# 02cpu_power.net
KiCad netlist of a schematic drawn in Altium Designer
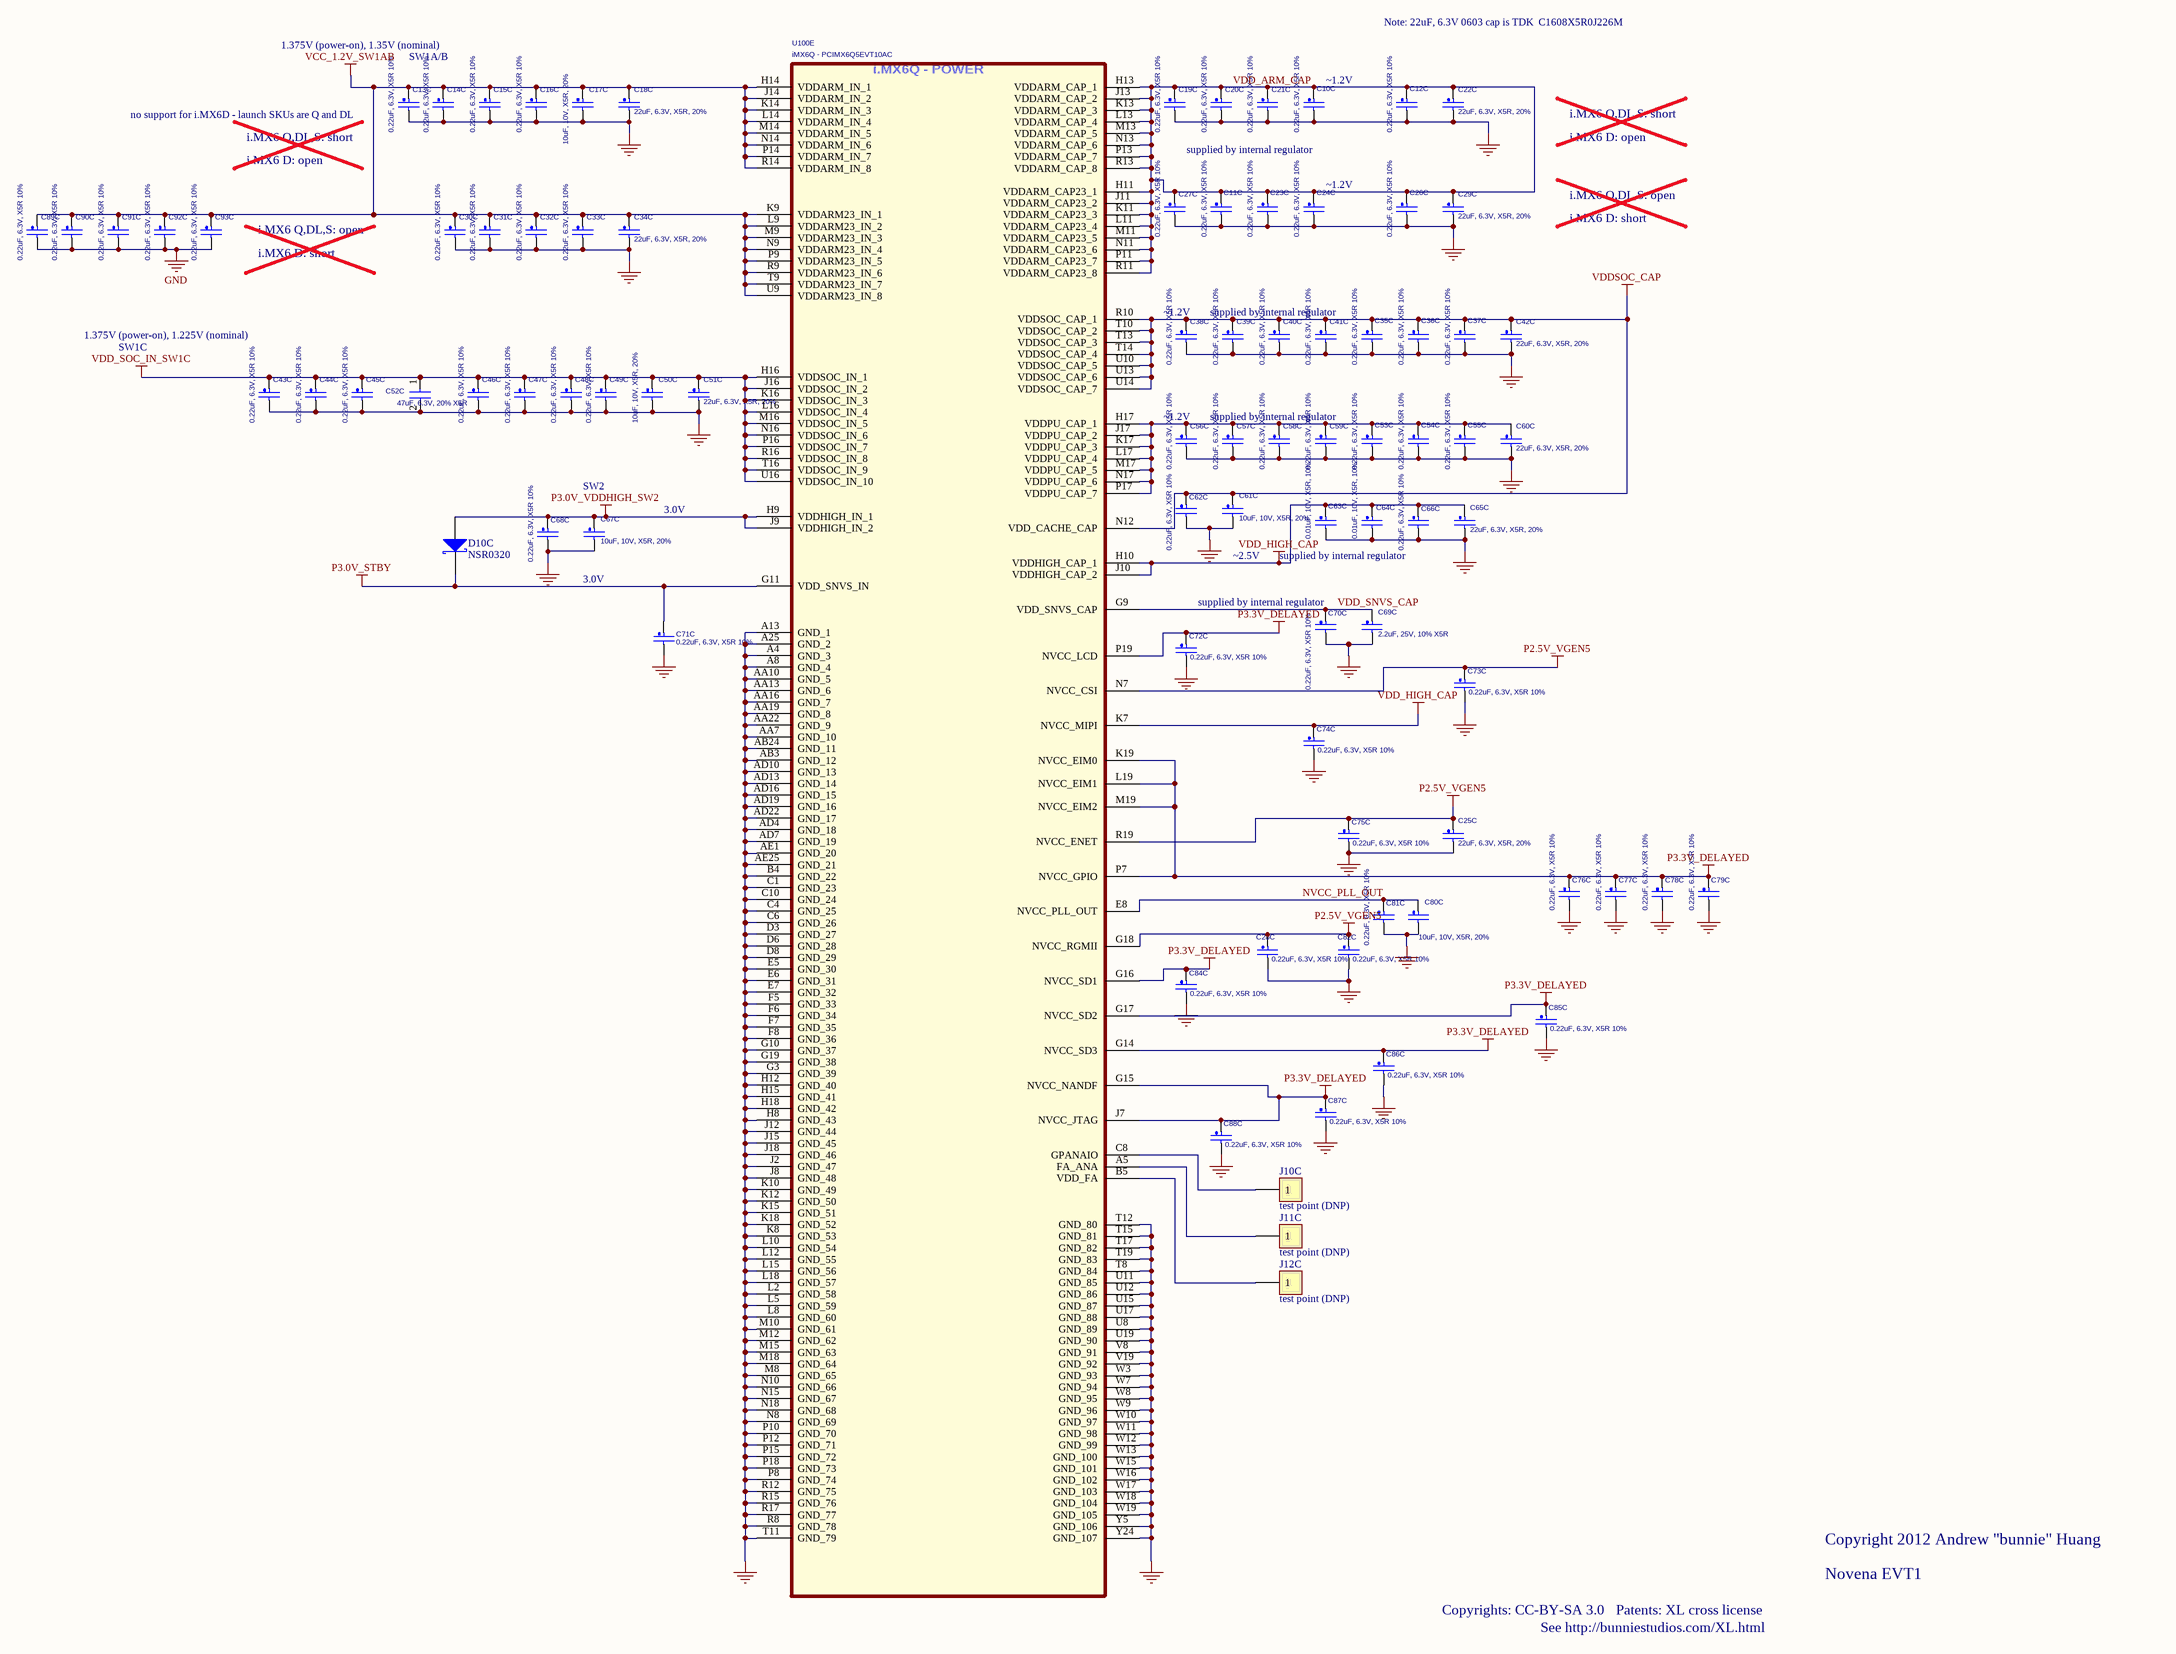
[diagram p0: 02cpu_power.SchDoc]

(export (version "E")
  (design (tool "Eeschema 10.0.6"))
  (components
    (comp (ref "C10C")
      (value "0.22uF, 6.3V, X5R 10%")
      (footprint "CAPC0603N_B")
      (description "CAP CER 0.01UF 6.3V 10% X7R 0201")
      (fields (field (name "TOLERANCE") "10%"))
      (libsource (lib "*") (part "CAP_NP_Dup1"))
    )
    (comp (ref "C11C")
      (value "0.22uF, 6.3V, X5R 10%")
      (footprint "CAPC0603N_B")
      (description "CAP CER 0.01UF 6.3V 10% X7R 0201")
      (fields (field (name "TOLERANCE") "10%"))
      (libsource (lib "*") (part "CAP_NP_Dup1"))
    )
    (comp (ref "C12C")
      (value "0.22uF, 6.3V, X5R 10%")
      (footprint "CAPC0603N_B")
      (description "CAP CER 0.01UF 6.3V 10% X7R 0201")
      (fields (field (name "TOLERANCE") "10%"))
      (libsource (lib "*") (part "CAP_NP_Dup1"))
    )
    (comp (ref "C13C")
      (value "0.22uF, 6.3V, X5R 10%")
      (footprint "CAPC0603N_B")
      (description "CAP CER 0.22UF 6.3V 20% X5R 0201")
      (fields (field (name "TOLERANCE") "20%"))
      (libsource (lib "*") (part "CAP_NP_Dup1"))
    )
    (comp (ref "C14C")
      (value "0.22uF, 6.3V, X5R 10%")
      (footprint "CAPC0603N_B")
      (description "CAP CER 0.22UF 6.3V 20% X5R 0201")
      (fields (field (name "TOLERANCE") "20%"))
      (libsource (lib "*") (part "CAP_NP_Dup1"))
    )
    (comp (ref "C15C")
      (value "0.22uF, 6.3V, X5R 10%")
      (footprint "CAPC0603N_B")
      (description "CAP CER 0.22UF 6.3V 20% X5R 0201")
      (fields (field (name "TOLERANCE") "20%"))
      (libsource (lib "*") (part "CAP_NP_Dup1"))
    )
    (comp (ref "C16C")
      (value "0.22uF, 6.3V, X5R 10%")
      (footprint "CAPC0603N_B")
      (description "CAP CER 0.22UF 6.3V 20% X5R 0201")
      (fields (field (name "TOLERANCE") "20%"))
      (libsource (lib "*") (part "CAP_NP_Dup1"))
    )
    (comp (ref "C17C")
      (value "10uF, 10V, X5R, 20%")
      (footprint "CAPC1608N_HD")
      (description "CAP CER 10UF 6.3V 10% X5R 0603")
      (fields (field (name "TOLERANCE") "10%"))
      (libsource (lib "*") (part "CAP_NP_Dup1"))
    )
    (comp (ref "C18C")
      (value "22uF, 6.3V, X5R, 20%")
      (footprint "CAPC1608N_HD")
      (description "CAP CER 22UF 6.3V 20% X5R 0805")
      (fields (field (name "TOLERANCE") "20%"))
      (libsource (lib "*") (part "CAP_NP_Dup1"))
    )
    (comp (ref "C19C")
      (value "0.22uF, 6.3V, X5R 10%")
      (footprint "CAPC0603N_B")
      (description "CAP CER 0.22UF 6.3V 20% X5R 0201")
      (fields (field (name "TOLERANCE") "20%"))
      (libsource (lib "*") (part "CAP_NP_Dup1"))
    )
    (comp (ref "C20C")
      (value "0.22uF, 6.3V, X5R 10%")
      (footprint "CAPC0603N_B")
      (description "CAP CER 0.22UF 6.3V 20% X5R 0201")
      (fields (field (name "TOLERANCE") "20%"))
      (libsource (lib "*") (part "CAP_NP_Dup1"))
    )
    (comp (ref "C21C")
      (value "0.22uF, 6.3V, X5R 10%")
      (footprint "CAPC0603N_B")
      (description "CAP CER 0.22UF 6.3V 20% X5R 0201")
      (fields (field (name "TOLERANCE") "20%"))
      (libsource (lib "*") (part "CAP_NP_Dup1"))
    )
    (comp (ref "C22C")
      (value "22uF, 6.3V, X5R, 20%")
      (footprint "CAPC1608N_HD")
      (description "CAP CER 22UF 6.3V 20% X5R 0805")
      (fields (field (name "TOLERANCE") "20%"))
      (libsource (lib "*") (part "CAP_NP_Dup1"))
    )
    (comp (ref "C23C")
      (value "0.22uF, 6.3V, X5R 10%")
      (footprint "CAPC0603N_B")
      (description "CAP CER 0.22UF 6.3V 20% X5R 0201")
      (fields (field (name "TOLERANCE") "20%"))
      (libsource (lib "*") (part "CAP_NP_Dup1"))
    )
    (comp (ref "C24C")
      (value "0.22uF, 6.3V, X5R 10%")
      (footprint "CAPC0603N_B")
      (description "CAP CER 0.01UF 6.3V 10% X7R 0201")
      (fields (field (name "TOLERANCE") "10%"))
      (libsource (lib "*") (part "CAP_NP_Dup1"))
    )
    (comp (ref "C25C")
      (value "22uF, 6.3V, X5R, 20%")
      (footprint "CAPC1608N_HD")
      (description "CAP CER 22UF 6.3V 20% X5R 0805")
      (fields (field (name "TOLERANCE") "20%"))
      (libsource (lib "*") (part "CAP_NP_Dup1"))
    )
    (comp (ref "C26C")
      (value "0.22uF, 6.3V, X5R 10%")
      (footprint "CAPC0603N_B")
      (description "CAP CER 0.01UF 6.3V 10% X7R 0201")
      (fields (field (name "TOLERANCE") "10%"))
      (libsource (lib "*") (part "CAP_NP_Dup1"))
    )
    (comp (ref "C27C")
      (value "0.22uF, 6.3V, X5R 10%")
      (footprint "CAPC0603N_B")
      (description "CAP CER 0.22UF 6.3V 20% X5R 0201")
      (fields (field (name "TOLERANCE") "20%"))
      (libsource (lib "*") (part "CAP_NP_Dup1"))
    )
    (comp (ref "C28C")
      (value "0.22uF, 6.3V, X5R 10%")
      (footprint "CAPC0603N_B")
      (description "CAP CER 0.22UF 6.3V 20% X5R 0201")
      (fields (field (name "TOLERANCE") "20%"))
      (libsource (lib "*") (part "CAP_NP_Dup1"))
    )
    (comp (ref "C29C")
      (value "22uF, 6.3V, X5R, 20%")
      (footprint "CAPC1608N_HD")
      (description "CAP CER 22UF 6.3V 20% X5R 0805")
      (fields (field (name "TOLERANCE") "20%"))
      (libsource (lib "*") (part "CAP_NP_Dup1"))
    )
    (comp (ref "C30C")
      (value "0.22uF, 6.3V, X5R 10%")
      (footprint "CAPC0603N_B")
      (description "CAP CER 0.22UF 6.3V 20% X5R 0201")
      (fields (field (name "TOLERANCE") "20%"))
      (libsource (lib "*") (part "CAP_NP_Dup1"))
    )
    (comp (ref "C31C")
      (value "0.22uF, 6.3V, X5R 10%")
      (footprint "CAPC0603N_B")
      (description "CAP CER 0.22UF 6.3V 20% X5R 0201")
      (fields (field (name "TOLERANCE") "20%"))
      (libsource (lib "*") (part "CAP_NP_Dup1"))
    )
    (comp (ref "C32C")
      (value "0.22uF, 6.3V, X5R 10%")
      (footprint "CAPC0603N_B")
      (description "CAP CER 0.22UF 6.3V 20% X5R 0201")
      (fields (field (name "TOLERANCE") "20%"))
      (libsource (lib "*") (part "CAP_NP_Dup1"))
    )
    (comp (ref "C33C")
      (value "0.22uF, 6.3V, X5R 10%")
      (footprint "CAPC0603N_B")
      (description "CAP CER 0.22UF 6.3V 20% X5R 0201")
      (fields (field (name "TOLERANCE") "20%"))
      (libsource (lib "*") (part "CAP_NP_Dup1"))
    )
    (comp (ref "C34C")
      (value "22uF, 6.3V, X5R, 20%")
      (footprint "CAPC1608N_HD")
      (description "CAP CER 22UF 6.3V 20% X5R 0805")
      (fields (field (name "TOLERANCE") "20%"))
      (libsource (lib "*") (part "CAP_NP_Dup1"))
    )
    (comp (ref "C35C")
      (value "0.22uF, 6.3V, X5R 10%")
      (footprint "CAPC0603N_B")
      (description "CAP CER 0.01UF 6.3V 10% X7R 0201")
      (fields (field (name "TOLERANCE") "10%"))
      (libsource (lib "*") (part "CAP_NP_Dup1"))
    )
    (comp (ref "C36C")
      (value "0.22uF, 6.3V, X5R 10%")
      (footprint "CAPC0603N_B")
      (description "CAP CER 0.01UF 6.3V 10% X7R 0201")
      (fields (field (name "TOLERANCE") "10%"))
      (libsource (lib "*") (part "CAP_NP_Dup1"))
    )
    (comp (ref "C37C")
      (value "0.22uF, 6.3V, X5R 10%")
      (footprint "CAPC0603N_B")
      (description "CAP CER 0.01UF 6.3V 10% X7R 0201")
      (fields (field (name "TOLERANCE") "10%"))
      (libsource (lib "*") (part "CAP_NP_Dup1"))
    )
    (comp (ref "C38C")
      (value "0.22uF, 6.3V, X5R 10%")
      (footprint "CAPC0603N_B")
      (description "CAP CER 0.22UF 6.3V 20% X5R 0201")
      (fields (field (name "TOLERANCE") "20%"))
      (libsource (lib "*") (part "CAP_NP_Dup1"))
    )
    (comp (ref "C39C")
      (value "0.22uF, 6.3V, X5R 10%")
      (footprint "CAPC0603N_B")
      (description "CAP CER 0.22UF 6.3V 20% X5R 0201")
      (fields (field (name "TOLERANCE") "20%"))
      (libsource (lib "*") (part "CAP_NP_Dup1"))
    )
    (comp (ref "C40C")
      (value "0.22uF, 6.3V, X5R 10%")
      (footprint "CAPC0603N_B")
      (description "CAP CER 0.22UF 6.3V 20% X5R 0201")
      (fields (field (name "TOLERANCE") "20%"))
      (libsource (lib "*") (part "CAP_NP_Dup1"))
    )
    (comp (ref "C41C")
      (value "0.22uF, 6.3V, X5R 10%")
      (footprint "CAPC0603N_B")
      (description "CAP CER 0.22UF 6.3V 20% X5R 0201")
      (fields (field (name "TOLERANCE") "20%"))
      (libsource (lib "*") (part "CAP_NP_Dup1"))
    )
    (comp (ref "C42C")
      (value "22uF, 6.3V, X5R, 20%")
      (footprint "CAPC1608N_HD")
      (description "CAP CER 22UF 6.3V 20% X5R 0805")
      (fields (field (name "TOLERANCE") "20%"))
      (libsource (lib "*") (part "CAP_NP_Dup1"))
    )
    (comp (ref "C43C")
      (value "0.22uF, 6.3V, X5R 10%")
      (footprint "CAPC0603N_B")
      (description "CAP CER 0.22UF 6.3V 20% X5R 0201")
      (fields (field (name "TOLERANCE") "20%"))
      (libsource (lib "*") (part "CAP_NP_Dup1"))
    )
    (comp (ref "C44C")
      (value "0.22uF, 6.3V, X5R 10%")
      (footprint "CAPC0603N_B")
      (description "CAP CER 0.22UF 6.3V 20% X5R 0201")
      (fields (field (name "TOLERANCE") "20%"))
      (libsource (lib "*") (part "CAP_NP_Dup1"))
    )
    (comp (ref "C45C")
      (value "0.22uF, 6.3V, X5R 10%")
      (footprint "CAPC0603N_B")
      (description "CAP CER 0.22UF 6.3V 20% X5R 0201")
      (fields (field (name "TOLERANCE") "20%"))
      (libsource (lib "*") (part "CAP_NP_Dup1"))
    )
    (comp (ref "C46C")
      (value "0.22uF, 6.3V, X5R 10%")
      (footprint "CAPC0603N_B")
      (description "CAP CER 0.22UF 6.3V 20% X5R 0201")
      (fields (field (name "TOLERANCE") "20%"))
      (libsource (lib "*") (part "CAP_NP_Dup1"))
    )
    (comp (ref "C47C")
      (value "0.22uF, 6.3V, X5R 10%")
      (footprint "CAPC0603N_B")
      (description "CAP CER 0.22UF 6.3V 20% X5R 0201")
      (fields (field (name "TOLERANCE") "20%"))
      (libsource (lib "*") (part "CAP_NP_Dup1"))
    )
    (comp (ref "C48C")
      (value "0.22uF, 6.3V, X5R 10%")
      (footprint "CAPC0603N_B")
      (description "CAP CER 0.22UF 6.3V 20% X5R 0201")
      (fields (field (name "TOLERANCE") "20%"))
      (libsource (lib "*") (part "CAP_NP_Dup1"))
    )
    (comp (ref "C49C")
      (value "0.22uF, 6.3V, X5R 10%")
      (footprint "CAPC0603N_B")
      (description "CAP CER 0.22UF 6.3V 20% X5R 0201")
      (fields (field (name "TOLERANCE") "20%"))
      (libsource (lib "*") (part "CAP_NP_Dup1"))
    )
    (comp (ref "C50C")
      (value "10uF, 10V, X5R, 20%")
      (footprint "CAPC1608N_HD")
      (description "CAP CER 10UF 6.3V 10% X5R 0603")
      (fields (field (name "TOLERANCE") "10%"))
      (libsource (lib "*") (part "CAP_NP_Dup1"))
    )
    (comp (ref "C51C")
      (value "22uF, 6.3V, X5R, 20%")
      (footprint "CAPC1608N_HD")
      (description "CAP CER 22UF 6.3V 20% X5R 0805")
      (fields (field (name "TOLERANCE") "20%"))
      (libsource (lib "*") (part "CAP_NP_Dup1"))
    )
    (comp (ref "C52C") (value "47uF, 6.3V, 20% X5R") (footprint "CAPC3216N") (libsource (lib "*") (part "C")))
    (comp (ref "C53C")
      (value "0.22uF, 6.3V, X5R 10%")
      (footprint "CAPC0603N_B")
      (description "CAP CER 0.01UF 6.3V 10% X7R 0201")
      (fields (field (name "TOLERANCE") "10%"))
      (libsource (lib "*") (part "CAP_NP_Dup1"))
    )
    (comp (ref "C54C")
      (value "0.22uF, 6.3V, X5R 10%")
      (footprint "CAPC0603N_B")
      (description "CAP CER 0.01UF 6.3V 10% X7R 0201")
      (fields (field (name "TOLERANCE") "10%"))
      (libsource (lib "*") (part "CAP_NP_Dup1"))
    )
    (comp (ref "C55C")
      (value "0.22uF, 6.3V, X5R 10%")
      (footprint "CAPC0603N_B")
      (description "CAP CER 0.01UF 6.3V 10% X7R 0201")
      (fields (field (name "TOLERANCE") "10%"))
      (libsource (lib "*") (part "CAP_NP_Dup1"))
    )
    (comp (ref "C56C")
      (value "0.22uF, 6.3V, X5R 10%")
      (footprint "CAPC0603N_B")
      (description "CAP CER 0.22UF 6.3V 20% X5R 0201")
      (fields (field (name "TOLERANCE") "20%"))
      (libsource (lib "*") (part "CAP_NP_Dup1"))
    )
    (comp (ref "C57C")
      (value "0.22uF, 6.3V, X5R 10%")
      (footprint "CAPC0603N_B")
      (description "CAP CER 0.22UF 6.3V 20% X5R 0201")
      (fields (field (name "TOLERANCE") "20%"))
      (libsource (lib "*") (part "CAP_NP_Dup1"))
    )
    (comp (ref "C58C")
      (value "0.22uF, 6.3V, X5R 10%")
      (footprint "CAPC0603N_B")
      (description "CAP CER 0.22UF 6.3V 20% X5R 0201")
      (fields (field (name "TOLERANCE") "20%"))
      (libsource (lib "*") (part "CAP_NP_Dup1"))
    )
    (comp (ref "C59C")
      (value "0.22uF, 6.3V, X5R 10%")
      (footprint "CAPC0603N_B")
      (description "CAP CER 0.22UF 6.3V 20% X5R 0201")
      (fields (field (name "TOLERANCE") "20%"))
      (libsource (lib "*") (part "CAP_NP_Dup1"))
    )
    (comp (ref "C60C")
      (value "22uF, 6.3V, X5R, 20%")
      (footprint "CAPC1608N_HD")
      (description "CAP CER 22UF 6.3V 20% X5R 0805")
      (fields (field (name "TOLERANCE") "20%"))
      (libsource (lib "*") (part "CAP_NP_Dup1"))
    )
    (comp (ref "C61C")
      (value "10uF, 10V, X5R, 20%")
      (footprint "CAPC1608N_HD")
      (description "CAP CER 10UF 6.3V 10% X5R 0603")
      (fields (field (name "TOLERANCE") "10%"))
      (libsource (lib "*") (part "CAP_NP_Dup1"))
    )
    (comp (ref "C62C")
      (value "0.22uF, 6.3V, X5R 10%")
      (footprint "CAPC0603N_B")
      (description "CAP CER 0.22UF 6.3V 20% X5R 0201")
      (fields (field (name "TOLERANCE") "20%"))
      (libsource (lib "*") (part "CAP_NP_Dup1"))
    )
    (comp (ref "C63C")
      (value "0.01uF, 10V, X5R, 10%")
      (footprint "CAPC0603N_B")
      (description "CAP CER 0.01UF 6.3V 10% X7R 0201")
      (fields (field (name "TOLERANCE") "10%"))
      (libsource (lib "*") (part "CAP_NP_Dup1"))
    )
    (comp (ref "C64C")
      (value "0.01uF, 10V, X5R, 10%")
      (footprint "CAPC0603N_B")
      (description "CAP CER 0.01UF 6.3V 10% X7R 0201")
      (fields (field (name "TOLERANCE") "10%"))
      (libsource (lib "*") (part "CAP_NP_Dup1"))
    )
    (comp (ref "C65C")
      (value "22uF, 6.3V, X5R, 20%")
      (footprint "CAPC1608N_HD")
      (description "CAP CER 22UF 6.3V 20% X5R 0805")
      (fields (field (name "TOLERANCE") "20%"))
      (libsource (lib "*") (part "CAP_NP_Dup1"))
    )
    (comp (ref "C66C")
      (value "0.22uF, 6.3V, X5R 10%")
      (footprint "CAPC0603N_B")
      (description "CAP CER 0.22UF 6.3V 20% X5R 0201")
      (fields (field (name "TOLERANCE") "20%"))
      (libsource (lib "*") (part "CAP_NP_Dup1"))
    )
    (comp (ref "C67C")
      (value "10uF, 10V, X5R, 20%")
      (footprint "CAPC1608N_HD")
      (description "CAP CER 10UF 6.3V 10% X5R 0603")
      (fields (field (name "TOLERANCE") "10%"))
      (libsource (lib "*") (part "CAP_NP_Dup1"))
    )
    (comp (ref "C68C")
      (value "0.22uF, 6.3V, X5R 10%")
      (footprint "CAPC0603N_B")
      (description "CAP CER 0.22UF 6.3V 20% X5R 0201")
      (fields (field (name "TOLERANCE") "20%"))
      (libsource (lib "*") (part "CAP_NP_Dup1"))
    )
    (comp (ref "C69C")
      (value "2.2uF, 25V, 10% X5R")
      (footprint "CAPC1608N_HD")
      (description "CAP CER 10UF 6.3V 10% X5R 0603")
      (fields (field (name "TOLERANCE") "10%"))
      (libsource (lib "*") (part "CAP_NP_Dup1"))
    )
    (comp (ref "C70C")
      (value "0.22uF, 6.3V, X5R 10%")
      (footprint "CAPC0603N_B")
      (description "CAP CER 0.22UF 6.3V 20% X5R 0201")
      (fields (field (name "TOLERANCE") "20%"))
      (libsource (lib "*") (part "CAP_NP_Dup1"))
    )
    (comp (ref "C71C")
      (value "0.22uF, 6.3V, X5R 10%")
      (footprint "CAPC0603N_B")
      (description "CAP CER 0.22UF 6.3V 20% X5R 0201")
      (fields (field (name "TOLERANCE") "20%"))
      (libsource (lib "*") (part "CAP_NP_Dup1"))
    )
    (comp (ref "C72C")
      (value "0.22uF, 6.3V, X5R 10%")
      (footprint "CAPC0603N_B")
      (description "CAP CER 0.22UF 6.3V 20% X5R 0201")
      (fields (field (name "TOLERANCE") "20%"))
      (libsource (lib "*") (part "CAP_NP_Dup1"))
    )
    (comp (ref "C73C")
      (value "0.22uF, 6.3V, X5R 10%")
      (footprint "CAPC0603N_B")
      (description "CAP CER 0.22UF 6.3V 20% X5R 0201")
      (fields (field (name "TOLERANCE") "20%"))
      (libsource (lib "*") (part "CAP_NP_Dup1"))
    )
    (comp (ref "C74C")
      (value "0.22uF, 6.3V, X5R 10%")
      (footprint "CAPC0603N_B")
      (description "CAP CER 0.22UF 6.3V 20% X5R 0201")
      (fields (field (name "TOLERANCE") "20%"))
      (libsource (lib "*") (part "CAP_NP_Dup1"))
    )
    (comp (ref "C75C")
      (value "0.22uF, 6.3V, X5R 10%")
      (footprint "CAPC0603N_B")
      (description "CAP CER 0.22UF 6.3V 20% X5R 0201")
      (fields (field (name "TOLERANCE") "20%"))
      (libsource (lib "*") (part "CAP_NP_Dup1"))
    )
    (comp (ref "C76C")
      (value "0.22uF, 6.3V, X5R 10%")
      (footprint "CAPC0603N_B")
      (description "CAP CER 0.22UF 6.3V 20% X5R 0201")
      (fields (field (name "TOLERANCE") "20%"))
      (libsource (lib "*") (part "CAP_NP_Dup1"))
    )
    (comp (ref "C77C")
      (value "0.22uF, 6.3V, X5R 10%")
      (footprint "CAPC0603N_B")
      (description "CAP CER 0.22UF 6.3V 20% X5R 0201")
      (fields (field (name "TOLERANCE") "20%"))
      (libsource (lib "*") (part "CAP_NP_Dup1"))
    )
    (comp (ref "C78C")
      (value "0.22uF, 6.3V, X5R 10%")
      (footprint "CAPC0603N_B")
      (description "CAP CER 0.22UF 6.3V 20% X5R 0201")
      (fields (field (name "TOLERANCE") "20%"))
      (libsource (lib "*") (part "CAP_NP_Dup1"))
    )
    (comp (ref "C79C")
      (value "0.22uF, 6.3V, X5R 10%")
      (footprint "CAPC0603N_B")
      (description "CAP CER 0.22UF 6.3V 20% X5R 0201")
      (fields (field (name "TOLERANCE") "20%"))
      (libsource (lib "*") (part "CAP_NP_Dup1"))
    )
    (comp (ref "C80C")
      (value "10uF, 10V, X5R, 20%")
      (footprint "CAPC1608N_HD")
      (description "CAP CER 10UF 6.3V 10% X5R 0603")
      (fields (field (name "TOLERANCE") "10%"))
      (libsource (lib "*") (part "CAP_NP_Dup1"))
    )
    (comp (ref "C81C")
      (value "0.22uF, 6.3V, X5R 10%")
      (footprint "CAPC0603N_B")
      (description "CAP CER 0.22UF 6.3V 20% X5R 0201")
      (fields (field (name "TOLERANCE") "20%"))
      (libsource (lib "*") (part "CAP_NP_Dup1"))
    )
    (comp (ref "C82C")
      (value "0.22uF, 6.3V, X5R 10%")
      (footprint "CAPC0603N_B")
      (description "CAP CER 0.22UF 6.3V 20% X5R 0201")
      (fields (field (name "TOLERANCE") "20%"))
      (libsource (lib "*") (part "CAP_NP_Dup1"))
    )
    (comp (ref "C84C")
      (value "0.22uF, 6.3V, X5R 10%")
      (footprint "CAPC0603N_B")
      (description "CAP CER 0.22UF 6.3V 20% X5R 0201")
      (fields (field (name "TOLERANCE") "20%"))
      (libsource (lib "*") (part "CAP_NP_Dup1"))
    )
    (comp (ref "C85C")
      (value "0.22uF, 6.3V, X5R 10%")
      (footprint "CAPC0603N_B")
      (description "CAP CER 0.22UF 6.3V 20% X5R 0201")
      (fields (field (name "TOLERANCE") "20%"))
      (libsource (lib "*") (part "CAP_NP_Dup1"))
    )
    (comp (ref "C86C")
      (value "0.22uF, 6.3V, X5R 10%")
      (footprint "CAPC0603N_B")
      (description "CAP CER 0.22UF 6.3V 20% X5R 0201")
      (fields (field (name "TOLERANCE") "20%"))
      (libsource (lib "*") (part "CAP_NP_Dup1"))
    )
    (comp (ref "C87C")
      (value "0.22uF, 6.3V, X5R 10%")
      (footprint "CAPC0603N_B")
      (description "CAP CER 0.22UF 6.3V 20% X5R 0201")
      (fields (field (name "TOLERANCE") "20%"))
      (libsource (lib "*") (part "CAP_NP_Dup1"))
    )
    (comp (ref "C88C")
      (value "0.22uF, 6.3V, X5R 10%")
      (footprint "CAPC0603N_B")
      (description "CAP CER 0.22UF 6.3V 20% X5R 0201")
      (fields (field (name "TOLERANCE") "20%"))
      (libsource (lib "*") (part "CAP_NP_Dup1"))
    )
    (comp (ref "C89C")
      (value "0.22uF, 6.3V, X5R 10%")
      (footprint "CAPC0603N_B")
      (description "CAP CER 0.22UF 6.3V 20% X5R 0201")
      (fields (field (name "TOLERANCE") "20%"))
      (libsource (lib "*") (part "CAP_NP_Dup1"))
    )
    (comp (ref "C90C")
      (value "0.22uF, 6.3V, X5R 10%")
      (footprint "CAPC0603N_B")
      (description "CAP CER 0.22UF 6.3V 20% X5R 0201")
      (fields (field (name "TOLERANCE") "20%"))
      (libsource (lib "*") (part "CAP_NP_Dup1"))
    )
    (comp (ref "C91C")
      (value "0.22uF, 6.3V, X5R 10%")
      (footprint "CAPC0603N_B")
      (description "CAP CER 0.22UF 6.3V 20% X5R 0201")
      (fields (field (name "TOLERANCE") "20%"))
      (libsource (lib "*") (part "CAP_NP_Dup1"))
    )
    (comp (ref "C92C")
      (value "0.22uF, 6.3V, X5R 10%")
      (footprint "CAPC0603N_B")
      (description "CAP CER 0.22UF 6.3V 20% X5R 0201")
      (fields (field (name "TOLERANCE") "20%"))
      (libsource (lib "*") (part "CAP_NP_Dup1"))
    )
    (comp (ref "C93C")
      (value "0.22uF, 6.3V, X5R 10%")
      (footprint "CAPC0603N_B")
      (description "CAP CER 0.22UF 6.3V 20% X5R 0201")
      (fields (field (name "TOLERANCE") "20%"))
      (libsource (lib "*") (part "CAP_NP_Dup1"))
    )
    (comp (ref "D10C")
      (value "NSR0320")
      (footprint "SOD-323")
      (description "Schottky Diode")
      (fields (field (name "PUBLISHER") "Altium Limited"))
      (libsource (lib "Miscellaneous Devices") (part "D Schottky"))
    )
    (comp (ref "J10C")
      (value "test point (DNP)")
      (footprint "TP_SMT_38mil")
      (description "Connector")
      (libsource (lib "*") (part "CON1"))
    )
    (comp (ref "J11C")
      (value "test point (DNP)")
      (footprint "TP_SMT_38mil")
      (description "Connector")
      (libsource (lib "*") (part "CON1"))
    )
    (comp (ref "J12C")
      (value "test point (DNP)")
      (footprint "TP_SMT_38mil")
      (description "Connector")
      (libsource (lib "*") (part "CON1"))
    )
    (comp (ref "U100")
      (value "iMX6Q - PCIMX6Q5EVT10AC")
      (description "PLACEHOLDER FOR FREESCALE PART NUMBER PMCIMX6Q6VV1A.")
      (libsource (lib "*") (part "PCIMX6Q6VV1A"))
    )
  )
  (nets
    (net (code "1") (name "/NVCC_PLL_OUT") (class "Default")
      (node (ref "C80C") (pin "1") (pinfunction "1_1") (pintype "passive"))
      (node (ref "C81C") (pin "1") (pinfunction "1_1") (pintype "passive"))
      (node (ref "U100") (pin "E8") (pinfunction "NVCC_PLL_OUT_E8") (pintype "power_in"))
    )
    (net (code "2") (name "/VDD_ARM_CAP") (class "Default")
      (node (ref "C10C") (pin "1") (pinfunction "1_1") (pintype "passive"))
      (node (ref "C11C") (pin "1") (pinfunction "1_1") (pintype "passive"))
      (node (ref "C12C") (pin "1") (pinfunction "1_1") (pintype "passive"))
      (node (ref "C19C") (pin "1") (pinfunction "1_1") (pintype "passive"))
      (node (ref "C20C") (pin "1") (pinfunction "1_1") (pintype "passive"))
      (node (ref "C21C") (pin "1") (pinfunction "1_1") (pintype "passive"))
      (node (ref "C22C") (pin "1") (pinfunction "1_1") (pintype "passive"))
      (node (ref "C23C") (pin "1") (pinfunction "1_1") (pintype "passive"))
      (node (ref "C24C") (pin "1") (pinfunction "1_1") (pintype "passive"))
      (node (ref "C26C") (pin "1") (pinfunction "1_1") (pintype "passive"))
      (node (ref "C27C") (pin "1") (pinfunction "1_1") (pintype "passive"))
      (node (ref "C29C") (pin "1") (pinfunction "1_1") (pintype "passive"))
      (node (ref "U100") (pin "H11") (pinfunction "VDDARM_CAP23_1_H11") (pintype "power_in"))
      (node (ref "U100") (pin "H13") (pinfunction "VDDARM_CAP_1_H13") (pintype "power_in"))
      (node (ref "U100") (pin "J11") (pinfunction "VDDARM_CAP23_2_J11") (pintype "power_in"))
      (node (ref "U100") (pin "J13") (pinfunction "VDDARM_CAP_2_J13") (pintype "power_in"))
      (node (ref "U100") (pin "K11") (pinfunction "VDDARM_CAP23_3_K11") (pintype "power_in"))
      (node (ref "U100") (pin "K13") (pinfunction "VDDARM_CAP_3_K13") (pintype "power_in"))
      (node (ref "U100") (pin "L11") (pinfunction "VDDARM_CAP23_4_L11") (pintype "power_in"))
      (node (ref "U100") (pin "L13") (pinfunction "VDDARM_CAP_4_L13") (pintype "power_in"))
      (node (ref "U100") (pin "M11") (pinfunction "VDDARM_CAP23_5_M11") (pintype "power_in"))
      (node (ref "U100") (pin "M13") (pinfunction "VDDARM_CAP_5_M13") (pintype "power_in"))
      (node (ref "U100") (pin "N11") (pinfunction "VDDARM_CAP23_6_N11") (pintype "power_in"))
      (node (ref "U100") (pin "N13") (pinfunction "VDDARM_CAP_6_N13") (pintype "power_in"))
      (node (ref "U100") (pin "P11") (pinfunction "VDDARM_CAP23_7_P11") (pintype "power_in"))
      (node (ref "U100") (pin "P13") (pinfunction "VDDARM_CAP_7_P13") (pintype "power_in"))
      (node (ref "U100") (pin "R11") (pinfunction "VDDARM_CAP23_8_R11") (pintype "power_in"))
      (node (ref "U100") (pin "R13") (pinfunction "VDDARM_CAP_8_R13") (pintype "power_in"))
    )
    (net (code "3") (name "/VDD_SNVS_CAP") (class "Default")
      (node (ref "C69C") (pin "1") (pinfunction "1_1") (pintype "passive"))
      (node (ref "C70C") (pin "1") (pinfunction "1_1") (pintype "passive"))
      (node (ref "U100") (pin "G9") (pinfunction "VDD_SNVS_CAP_G9") (pintype "power_in"))
    )
    (net (code "4") (name "GND") (class "Default")
      (node (ref "C10C") (pin "2") (pinfunction "2_2") (pintype "passive"))
      (node (ref "C11C") (pin "2") (pinfunction "2_2") (pintype "passive"))
      (node (ref "C12C") (pin "2") (pinfunction "2_2") (pintype "passive"))
      (node (ref "C13C") (pin "2") (pinfunction "2_2") (pintype "passive"))
      (node (ref "C14C") (pin "2") (pinfunction "2_2") (pintype "passive"))
      (node (ref "C15C") (pin "2") (pinfunction "2_2") (pintype "passive"))
      (node (ref "C16C") (pin "2") (pinfunction "2_2") (pintype "passive"))
      (node (ref "C17C") (pin "2") (pinfunction "2_2") (pintype "passive"))
      (node (ref "C18C") (pin "2") (pinfunction "2_2") (pintype "passive"))
      (node (ref "C19C") (pin "2") (pinfunction "2_2") (pintype "passive"))
      (node (ref "C20C") (pin "2") (pinfunction "2_2") (pintype "passive"))
      (node (ref "C21C") (pin "2") (pinfunction "2_2") (pintype "passive"))
      (node (ref "C22C") (pin "2") (pinfunction "2_2") (pintype "passive"))
      (node (ref "C23C") (pin "2") (pinfunction "2_2") (pintype "passive"))
      (node (ref "C24C") (pin "2") (pinfunction "2_2") (pintype "passive"))
      (node (ref "C25C") (pin "2") (pinfunction "2_2") (pintype "passive"))
      (node (ref "C26C") (pin "2") (pinfunction "2_2") (pintype "passive"))
      (node (ref "C27C") (pin "2") (pinfunction "2_2") (pintype "passive"))
      (node (ref "C28C") (pin "2") (pinfunction "2_2") (pintype "passive"))
      (node (ref "C29C") (pin "2") (pinfunction "2_2") (pintype "passive"))
      (node (ref "C30C") (pin "2") (pinfunction "2_2") (pintype "passive"))
      (node (ref "C31C") (pin "2") (pinfunction "2_2") (pintype "passive"))
      (node (ref "C32C") (pin "2") (pinfunction "2_2") (pintype "passive"))
      (node (ref "C33C") (pin "2") (pinfunction "2_2") (pintype "passive"))
      (node (ref "C34C") (pin "2") (pinfunction "2_2") (pintype "passive"))
      (node (ref "C35C") (pin "2") (pinfunction "2_2") (pintype "passive"))
      (node (ref "C36C") (pin "2") (pinfunction "2_2") (pintype "passive"))
      (node (ref "C37C") (pin "2") (pinfunction "2_2") (pintype "passive"))
      (node (ref "C38C") (pin "2") (pinfunction "2_2") (pintype "passive"))
      (node (ref "C39C") (pin "2") (pinfunction "2_2") (pintype "passive"))
      (node (ref "C40C") (pin "2") (pinfunction "2_2") (pintype "passive"))
      (node (ref "C41C") (pin "2") (pinfunction "2_2") (pintype "passive"))
      (node (ref "C42C") (pin "2") (pinfunction "2_2") (pintype "passive"))
      (node (ref "C43C") (pin "2") (pinfunction "2_2") (pintype "passive"))
      (node (ref "C44C") (pin "2") (pinfunction "2_2") (pintype "passive"))
      (node (ref "C45C") (pin "2") (pinfunction "2_2") (pintype "passive"))
      (node (ref "C46C") (pin "2") (pinfunction "2_2") (pintype "passive"))
      (node (ref "C47C") (pin "2") (pinfunction "2_2") (pintype "passive"))
      (node (ref "C48C") (pin "2") (pinfunction "2_2") (pintype "passive"))
      (node (ref "C49C") (pin "2") (pinfunction "2_2") (pintype "passive"))
      (node (ref "C50C") (pin "2") (pinfunction "2_2") (pintype "passive"))
      (node (ref "C51C") (pin "2") (pinfunction "2_2") (pintype "passive"))
      (node (ref "C52C") (pin "2") (pinfunction "2_2") (pintype "passive"))
      (node (ref "C53C") (pin "2") (pinfunction "2_2") (pintype "passive"))
      (node (ref "C54C") (pin "2") (pinfunction "2_2") (pintype "passive"))
      (node (ref "C55C") (pin "2") (pinfunction "2_2") (pintype "passive"))
      (node (ref "C56C") (pin "2") (pinfunction "2_2") (pintype "passive"))
      (node (ref "C57C") (pin "2") (pinfunction "2_2") (pintype "passive"))
      (node (ref "C58C") (pin "2") (pinfunction "2_2") (pintype "passive"))
      (node (ref "C59C") (pin "2") (pinfunction "2_2") (pintype "passive"))
      (node (ref "C60C") (pin "2") (pinfunction "2_2") (pintype "passive"))
      (node (ref "C61C") (pin "2") (pinfunction "2_2") (pintype "passive"))
      (node (ref "C62C") (pin "2") (pinfunction "2_2") (pintype "passive"))
      (node (ref "C63C") (pin "2") (pinfunction "2_2") (pintype "passive"))
      (node (ref "C64C") (pin "2") (pinfunction "2_2") (pintype "passive"))
      (node (ref "C65C") (pin "2") (pinfunction "2_2") (pintype "passive"))
      (node (ref "C66C") (pin "2") (pinfunction "2_2") (pintype "passive"))
      (node (ref "C67C") (pin "2") (pinfunction "2_2") (pintype "passive"))
      (node (ref "C68C") (pin "2") (pinfunction "2_2") (pintype "passive"))
      (node (ref "C69C") (pin "2") (pinfunction "2_2") (pintype "passive"))
      (node (ref "C70C") (pin "2") (pinfunction "2_2") (pintype "passive"))
      (node (ref "C71C") (pin "2") (pinfunction "2_2") (pintype "passive"))
      (node (ref "C72C") (pin "2") (pinfunction "2_2") (pintype "passive"))
      (node (ref "C73C") (pin "2") (pinfunction "2_2") (pintype "passive"))
      (node (ref "C74C") (pin "2") (pinfunction "2_2") (pintype "passive"))
      (node (ref "C75C") (pin "2") (pinfunction "2_2") (pintype "passive"))
      (node (ref "C76C") (pin "2") (pinfunction "2_2") (pintype "passive"))
      (node (ref "C77C") (pin "2") (pinfunction "2_2") (pintype "passive"))
      (node (ref "C78C") (pin "2") (pinfunction "2_2") (pintype "passive"))
      (node (ref "C79C") (pin "2") (pinfunction "2_2") (pintype "passive"))
      (node (ref "C80C") (pin "2") (pinfunction "2_2") (pintype "passive"))
      (node (ref "C81C") (pin "2") (pinfunction "2_2") (pintype "passive"))
      (node (ref "C82C") (pin "2") (pinfunction "2_2") (pintype "passive"))
      (node (ref "C84C") (pin "2") (pinfunction "2_2") (pintype "passive"))
      (node (ref "C85C") (pin "2") (pinfunction "2_2") (pintype "passive"))
      (node (ref "C86C") (pin "2") (pinfunction "2_2") (pintype "passive"))
      (node (ref "C87C") (pin "2") (pinfunction "2_2") (pintype "passive"))
      (node (ref "C88C") (pin "2") (pinfunction "2_2") (pintype "passive"))
      (node (ref "C89C") (pin "2") (pinfunction "2_2") (pintype "passive"))
      (node (ref "C90C") (pin "2") (pinfunction "2_2") (pintype "passive"))
      (node (ref "C91C") (pin "2") (pinfunction "2_2") (pintype "passive"))
      (node (ref "C92C") (pin "2") (pinfunction "2_2") (pintype "passive"))
      (node (ref "C93C") (pin "2") (pinfunction "2_2") (pintype "passive"))
      (node (ref "U100") (pin "A13") (pinfunction "GND_1_A13") (pintype "power_in"))
      (node (ref "U100") (pin "A25") (pinfunction "GND_2_A25") (pintype "power_in"))
      (node (ref "U100") (pin "A4") (pinfunction "GND_3_A4") (pintype "power_in"))
      (node (ref "U100") (pin "A8") (pinfunction "GND_4_A8") (pintype "power_in"))
      (node (ref "U100") (pin "AA10") (pinfunction "GND_5_AA10") (pintype "power_in"))
      (node (ref "U100") (pin "AA13") (pinfunction "GND_6_AA13") (pintype "power_in"))
      (node (ref "U100") (pin "AA16") (pinfunction "GND_7_AA16") (pintype "power_in"))
      (node (ref "U100") (pin "AA19") (pinfunction "GND_8_AA19") (pintype "power_in"))
      (node (ref "U100") (pin "AA22") (pinfunction "GND_9_AA22") (pintype "power_in"))
      (node (ref "U100") (pin "AA7") (pinfunction "GND_10_AA7") (pintype "power_in"))
      (node (ref "U100") (pin "AB24") (pinfunction "GND_11_AB24") (pintype "power_in"))
      (node (ref "U100") (pin "AB3") (pinfunction "GND_12_AB3") (pintype "power_in"))
      (node (ref "U100") (pin "AD10") (pinfunction "GND_13_AD10") (pintype "power_in"))
      (node (ref "U100") (pin "AD13") (pinfunction "GND_14_AD13") (pintype "power_in"))
      (node (ref "U100") (pin "AD16") (pinfunction "GND_15_AD16") (pintype "power_in"))
      (node (ref "U100") (pin "AD19") (pinfunction "GND_16_AD19") (pintype "power_in"))
      (node (ref "U100") (pin "AD22") (pinfunction "GND_17_AD22") (pintype "power_in"))
      (node (ref "U100") (pin "AD4") (pinfunction "GND_18_AD4") (pintype "power_in"))
      (node (ref "U100") (pin "AD7") (pinfunction "GND_19_AD7") (pintype "power_in"))
      (node (ref "U100") (pin "AE1") (pinfunction "GND_20_AE1") (pintype "power_in"))
      (node (ref "U100") (pin "AE25") (pinfunction "GND_21_AE25") (pintype "power_in"))
      (node (ref "U100") (pin "B4") (pinfunction "GND_22_B4") (pintype "power_in"))
      (node (ref "U100") (pin "C1") (pinfunction "GND_23_C1") (pintype "power_in"))
      (node (ref "U100") (pin "C10") (pinfunction "GND_24_C10") (pintype "power_in"))
      (node (ref "U100") (pin "C4") (pinfunction "GND_25_C4") (pintype "power_in"))
      (node (ref "U100") (pin "C6") (pinfunction "GND_26_C6") (pintype "power_in"))
      (node (ref "U100") (pin "D3") (pinfunction "GND_27_D3") (pintype "power_in"))
      (node (ref "U100") (pin "D6") (pinfunction "GND_28_D6") (pintype "power_in"))
      (node (ref "U100") (pin "D8") (pinfunction "GND_29_D8") (pintype "power_in"))
      (node (ref "U100") (pin "E5") (pinfunction "GND_30_E5") (pintype "power_in"))
      (node (ref "U100") (pin "E6") (pinfunction "GND_31_E6") (pintype "power_in"))
      (node (ref "U100") (pin "E7") (pinfunction "GND_32_E7") (pintype "power_in"))
      (node (ref "U100") (pin "F5") (pinfunction "GND_33_F5") (pintype "power_in"))
      (node (ref "U100") (pin "F6") (pinfunction "GND_34_F6") (pintype "power_in"))
      (node (ref "U100") (pin "F7") (pinfunction "GND_35_F7") (pintype "power_in"))
      (node (ref "U100") (pin "F8") (pinfunction "GND_36_F8") (pintype "power_in"))
      (node (ref "U100") (pin "G10") (pinfunction "GND_37_G10") (pintype "power_in"))
      (node (ref "U100") (pin "G19") (pinfunction "GND_38_G19") (pintype "power_in"))
      (node (ref "U100") (pin "G3") (pinfunction "GND_39_G3") (pintype "power_in"))
      (node (ref "U100") (pin "H12") (pinfunction "GND_40_H12") (pintype "power_in"))
      (node (ref "U100") (pin "H15") (pinfunction "GND_41_H15") (pintype "power_in"))
      (node (ref "U100") (pin "H18") (pinfunction "GND_42_H18") (pintype "power_in"))
      (node (ref "U100") (pin "H8") (pinfunction "GND_43_H8") (pintype "power_in"))
      (node (ref "U100") (pin "J12") (pinfunction "GND_44_J12") (pintype "power_in"))
      (node (ref "U100") (pin "J15") (pinfunction "GND_45_J15") (pintype "power_in"))
      (node (ref "U100") (pin "J18") (pinfunction "GND_46_J18") (pintype "power_in"))
      (node (ref "U100") (pin "J2") (pinfunction "GND_47_J2") (pintype "power_in"))
      (node (ref "U100") (pin "J8") (pinfunction "GND_48_J8") (pintype "power_in"))
      (node (ref "U100") (pin "K10") (pinfunction "GND_49_K10") (pintype "power_in"))
      (node (ref "U100") (pin "K12") (pinfunction "GND_50_K12") (pintype "power_in"))
      (node (ref "U100") (pin "K15") (pinfunction "GND_51_K15") (pintype "power_in"))
      (node (ref "U100") (pin "K18") (pinfunction "GND_52_K18") (pintype "power_in"))
      (node (ref "U100") (pin "K8") (pinfunction "GND_53_K8") (pintype "power_in"))
      (node (ref "U100") (pin "L10") (pinfunction "GND_54_L10") (pintype "power_in"))
      (node (ref "U100") (pin "L12") (pinfunction "GND_55_L12") (pintype "power_in"))
      (node (ref "U100") (pin "L15") (pinfunction "GND_56_L15") (pintype "power_in"))
      (node (ref "U100") (pin "L18") (pinfunction "GND_57_L18") (pintype "power_in"))
      (node (ref "U100") (pin "L2") (pinfunction "GND_58_L2") (pintype "power_in"))
      (node (ref "U100") (pin "L5") (pinfunction "GND_59_L5") (pintype "power_in"))
      (node (ref "U100") (pin "L8") (pinfunction "GND_60_L8") (pintype "power_in"))
      (node (ref "U100") (pin "M10") (pinfunction "GND_61_M10") (pintype "power_in"))
      (node (ref "U100") (pin "M12") (pinfunction "GND_62_M12") (pintype "power_in"))
      (node (ref "U100") (pin "M15") (pinfunction "GND_63_M15") (pintype "power_in"))
      (node (ref "U100") (pin "M18") (pinfunction "GND_64_M18") (pintype "power_in"))
      (node (ref "U100") (pin "M8") (pinfunction "GND_65_M8") (pintype "power_in"))
      (node (ref "U100") (pin "N10") (pinfunction "GND_66_N10") (pintype "power_in"))
      (node (ref "U100") (pin "N15") (pinfunction "GND_67_N15") (pintype "power_in"))
      (node (ref "U100") (pin "N18") (pinfunction "GND_68_N18") (pintype "power_in"))
      (node (ref "U100") (pin "N8") (pinfunction "GND_69_N8") (pintype "power_in"))
      (node (ref "U100") (pin "P10") (pinfunction "GND_70_P10") (pintype "power_in"))
      (node (ref "U100") (pin "P12") (pinfunction "GND_71_P12") (pintype "power_in"))
      (node (ref "U100") (pin "P15") (pinfunction "GND_72_P15") (pintype "power_in"))
      (node (ref "U100") (pin "P18") (pinfunction "GND_73_P18") (pintype "power_in"))
      (node (ref "U100") (pin "P8") (pinfunction "GND_74_P8") (pintype "power_in"))
      (node (ref "U100") (pin "R12") (pinfunction "GND_75_R12") (pintype "power_in"))
      (node (ref "U100") (pin "R15") (pinfunction "GND_76_R15") (pintype "power_in"))
      (node (ref "U100") (pin "R17") (pinfunction "GND_77_R17") (pintype "power_in"))
      (node (ref "U100") (pin "R8") (pinfunction "GND_78_R8") (pintype "power_in"))
      (node (ref "U100") (pin "T11") (pinfunction "GND_79_T11") (pintype "power_in"))
      (node (ref "U100") (pin "T12") (pinfunction "GND_80_T12") (pintype "power_in"))
      (node (ref "U100") (pin "T15") (pinfunction "GND_81_T15") (pintype "power_in"))
      (node (ref "U100") (pin "T17") (pinfunction "GND_82_T17") (pintype "power_in"))
      (node (ref "U100") (pin "T19") (pinfunction "GND_83_T19") (pintype "power_in"))
      (node (ref "U100") (pin "T8") (pinfunction "GND_84_T8") (pintype "power_in"))
      (node (ref "U100") (pin "U11") (pinfunction "GND_85_U11") (pintype "power_in"))
      (node (ref "U100") (pin "U12") (pinfunction "GND_86_U12") (pintype "power_in"))
      (node (ref "U100") (pin "U15") (pinfunction "GND_87_U15") (pintype "power_in"))
      (node (ref "U100") (pin "U17") (pinfunction "GND_88_U17") (pintype "power_in"))
      (node (ref "U100") (pin "U19") (pinfunction "GND_90_U19") (pintype "power_in"))
      (node (ref "U100") (pin "U8") (pinfunction "GND_89_U8") (pintype "power_in"))
      (node (ref "U100") (pin "V19") (pinfunction "GND_92_V19") (pintype "power_in"))
      (node (ref "U100") (pin "V8") (pinfunction "GND_91_V8") (pintype "power_in"))
      (node (ref "U100") (pin "W10") (pinfunction "GND_97_W10") (pintype "power_in"))
      (node (ref "U100") (pin "W11") (pinfunction "GND_98_W11") (pintype "power_in"))
      (node (ref "U100") (pin "W12") (pinfunction "GND_99_W12") (pintype "power_in"))
      (node (ref "U100") (pin "W13") (pinfunction "GND_100_W13") (pintype "power_in"))
      (node (ref "U100") (pin "W15") (pinfunction "GND_101_W15") (pintype "power_in"))
      (node (ref "U100") (pin "W16") (pinfunction "GND_102_W16") (pintype "power_in"))
      (node (ref "U100") (pin "W17") (pinfunction "GND_103_W17") (pintype "power_in"))
      (node (ref "U100") (pin "W18") (pinfunction "GND_104_W18") (pintype "power_in"))
      (node (ref "U100") (pin "W19") (pinfunction "GND_105_W19") (pintype "power_in"))
      (node (ref "U100") (pin "W3") (pinfunction "GND_93_W3") (pintype "power_in"))
      (node (ref "U100") (pin "W7") (pinfunction "GND_94_W7") (pintype "power_in"))
      (node (ref "U100") (pin "W8") (pinfunction "GND_95_W8") (pintype "power_in"))
      (node (ref "U100") (pin "W9") (pinfunction "GND_96_W9") (pintype "power_in"))
      (node (ref "U100") (pin "Y24") (pinfunction "GND_107_Y24") (pintype "power_in"))
      (node (ref "U100") (pin "Y5") (pinfunction "GND_106_Y5") (pintype "power_in"))
    )
    (net (code "5") (name "Net-(U100E-FA_ANA)") (class "Default")
      (node (ref "J11C") (pin "1") (pinfunction "1_1") (pintype "passive"))
      (node (ref "U100") (pin "A5") (pinfunction "FA_ANA_A5") (pintype "power_in"))
    )
    (net (code "6") (name "Net-(U100E-GPANAIO)") (class "Default")
      (node (ref "J10C") (pin "1") (pinfunction "1_1") (pintype "passive"))
      (node (ref "U100") (pin "C8") (pinfunction "GPANAIO_C8") (pintype "power_in"))
    )
    (net (code "7") (name "Net-(U100E-VDDPU_CAP_1)") (class "Default")
      (node (ref "C53C") (pin "1") (pinfunction "1_1") (pintype "passive"))
      (node (ref "C54C") (pin "1") (pinfunction "1_1") (pintype "passive"))
      (node (ref "C55C") (pin "1") (pinfunction "1_1") (pintype "passive"))
      (node (ref "C56C") (pin "1") (pinfunction "1_1") (pintype "passive"))
      (node (ref "C57C") (pin "1") (pinfunction "1_1") (pintype "passive"))
      (node (ref "C58C") (pin "1") (pinfunction "1_1") (pintype "passive"))
      (node (ref "C59C") (pin "1") (pinfunction "1_1") (pintype "passive"))
      (node (ref "C60C") (pin "1") (pinfunction "1_1") (pintype "passive"))
      (node (ref "U100") (pin "H17") (pinfunction "VDDPU_CAP_1_H17") (pintype "power_in"))
      (node (ref "U100") (pin "J17") (pinfunction "VDDPU_CAP_2_J17") (pintype "power_in"))
      (node (ref "U100") (pin "K17") (pinfunction "VDDPU_CAP_3_K17") (pintype "power_in"))
      (node (ref "U100") (pin "L17") (pinfunction "VDDPU_CAP_4_L17") (pintype "power_in"))
      (node (ref "U100") (pin "M17") (pinfunction "VDDPU_CAP_5_M17") (pintype "power_in"))
      (node (ref "U100") (pin "N17") (pinfunction "VDDPU_CAP_6_N17") (pintype "power_in"))
      (node (ref "U100") (pin "P17") (pinfunction "VDDPU_CAP_7_P17") (pintype "power_in"))
    )
    (net (code "8") (name "Net-(U100E-VDD_FA)") (class "Default")
      (node (ref "J12C") (pin "1") (pinfunction "1_1") (pintype "passive"))
      (node (ref "U100") (pin "B5") (pinfunction "VDD_FA_B5") (pintype "power_in"))
    )
    (net (code "9") (name "P2.5V_VGEN5") (class "Default")
      (node (ref "C25C") (pin "1") (pinfunction "1_1") (pintype "passive"))
      (node (ref "C28C") (pin "1") (pinfunction "1_1") (pintype "passive"))
      (node (ref "C73C") (pin "1") (pinfunction "1_1") (pintype "passive"))
      (node (ref "C75C") (pin "1") (pinfunction "1_1") (pintype "passive"))
      (node (ref "C82C") (pin "1") (pinfunction "1_1") (pintype "passive"))
      (node (ref "U100") (pin "G18") (pinfunction "NVCC_RGMII_G18") (pintype "power_in"))
      (node (ref "U100") (pin "N7") (pinfunction "NVCC_CSI_N7") (pintype "power_in"))
      (node (ref "U100") (pin "R19") (pinfunction "NVCC_ENET_R19") (pintype "power_in"))
    )
    (net (code "10") (name "P3.0V_STBY") (class "Default")
      (node (ref "C71C") (pin "1") (pinfunction "1_1") (pintype "passive"))
      (node (ref "D10C") (pin "2") (pinfunction "K_2") (pintype "passive"))
      (node (ref "U100") (pin "G11") (pinfunction "VDD_SNVS_IN_G11") (pintype "power_in"))
    )
    (net (code "11") (name "P3.0V_VDDHIGH_SW2") (class "Default")
      (node (ref "C67C") (pin "1") (pinfunction "1_1") (pintype "passive"))
      (node (ref "C68C") (pin "1") (pinfunction "1_1") (pintype "passive"))
      (node (ref "D10C") (pin "1") (pinfunction "A_1") (pintype "passive"))
      (node (ref "U100") (pin "H9") (pinfunction "VDDHIGH_IN_1_H9") (pintype "power_in"))
      (node (ref "U100") (pin "J9") (pinfunction "VDDHIGH_IN_2_J9") (pintype "power_in"))
    )
    (net (code "12") (name "P3.3V_DELAYED") (class "Default")
      (node (ref "C72C") (pin "1") (pinfunction "1_1") (pintype "passive"))
      (node (ref "C76C") (pin "1") (pinfunction "1_1") (pintype "passive"))
      (node (ref "C77C") (pin "1") (pinfunction "1_1") (pintype "passive"))
      (node (ref "C78C") (pin "1") (pinfunction "1_1") (pintype "passive"))
      (node (ref "C79C") (pin "1") (pinfunction "1_1") (pintype "passive"))
      (node (ref "C84C") (pin "1") (pinfunction "1_1") (pintype "passive"))
      (node (ref "C85C") (pin "1") (pinfunction "1_1") (pintype "passive"))
      (node (ref "C86C") (pin "1") (pinfunction "1_1") (pintype "passive"))
      (node (ref "C87C") (pin "1") (pinfunction "1_1") (pintype "passive"))
      (node (ref "C88C") (pin "1") (pinfunction "1_1") (pintype "passive"))
      (node (ref "U100") (pin "G14") (pinfunction "NVCC_SD3_G14") (pintype "power_in"))
      (node (ref "U100") (pin "G15") (pinfunction "NVCC_NANDF_G15") (pintype "power_in"))
      (node (ref "U100") (pin "G16") (pinfunction "NVCC_SD1_G16") (pintype "power_in"))
      (node (ref "U100") (pin "G17") (pinfunction "NVCC_SD2_G17") (pintype "power_in"))
      (node (ref "U100") (pin "J7") (pinfunction "NVCC_JTAG_J7") (pintype "power_in"))
      (node (ref "U100") (pin "K19") (pinfunction "NVCC_EIM0_K19") (pintype "power_in"))
      (node (ref "U100") (pin "L19") (pinfunction "NVCC_EIM1_L19") (pintype "power_in"))
      (node (ref "U100") (pin "M19") (pinfunction "NVCC_EIM2_M19") (pintype "power_in"))
      (node (ref "U100") (pin "P19") (pinfunction "NVCC_LCD_P19") (pintype "power_in"))
      (node (ref "U100") (pin "P7") (pinfunction "NVCC_GPIO_P7") (pintype "power_in"))
    )
    (net (code "13") (name "VCC_1.2V_SW1AB") (class "Default")
      (node (ref "C13C") (pin "1") (pinfunction "1_1") (pintype "passive"))
      (node (ref "C14C") (pin "1") (pinfunction "1_1") (pintype "passive"))
      (node (ref "C15C") (pin "1") (pinfunction "1_1") (pintype "passive"))
      (node (ref "C16C") (pin "1") (pinfunction "1_1") (pintype "passive"))
      (node (ref "C17C") (pin "1") (pinfunction "1_1") (pintype "passive"))
      (node (ref "C18C") (pin "1") (pinfunction "1_1") (pintype "passive"))
      (node (ref "C30C") (pin "1") (pinfunction "1_1") (pintype "passive"))
      (node (ref "C31C") (pin "1") (pinfunction "1_1") (pintype "passive"))
      (node (ref "C32C") (pin "1") (pinfunction "1_1") (pintype "passive"))
      (node (ref "C33C") (pin "1") (pinfunction "1_1") (pintype "passive"))
      (node (ref "C34C") (pin "1") (pinfunction "1_1") (pintype "passive"))
      (node (ref "C89C") (pin "1") (pinfunction "1_1") (pintype "passive"))
      (node (ref "C90C") (pin "1") (pinfunction "1_1") (pintype "passive"))
      (node (ref "C91C") (pin "1") (pinfunction "1_1") (pintype "passive"))
      (node (ref "C92C") (pin "1") (pinfunction "1_1") (pintype "passive"))
      (node (ref "C93C") (pin "1") (pinfunction "1_1") (pintype "passive"))
      (node (ref "U100") (pin "H14") (pinfunction "VDDARM_IN_1_H14") (pintype "power_in"))
      (node (ref "U100") (pin "J14") (pinfunction "VDDARM_IN_2_J14") (pintype "power_in"))
      (node (ref "U100") (pin "K14") (pinfunction "VDDARM_IN_3_K14") (pintype "power_in"))
      (node (ref "U100") (pin "K9") (pinfunction "VDDARM23_IN_1_K9") (pintype "power_in"))
      (node (ref "U100") (pin "L14") (pinfunction "VDDARM_IN_4_L14") (pintype "power_in"))
      (node (ref "U100") (pin "L9") (pinfunction "VDDARM23_IN_2_L9") (pintype "power_in"))
      (node (ref "U100") (pin "M14") (pinfunction "VDDARM_IN_5_M14") (pintype "power_in"))
      (node (ref "U100") (pin "M9") (pinfunction "VDDARM23_IN_3_M9") (pintype "power_in"))
      (node (ref "U100") (pin "N14") (pinfunction "VDDARM_IN_6_N14") (pintype "power_in"))
      (node (ref "U100") (pin "N9") (pinfunction "VDDARM23_IN_4_N9") (pintype "power_in"))
      (node (ref "U100") (pin "P14") (pinfunction "VDDARM_IN_7_P14") (pintype "power_in"))
      (node (ref "U100") (pin "P9") (pinfunction "VDDARM23_IN_5_P9") (pintype "power_in"))
      (node (ref "U100") (pin "R14") (pinfunction "VDDARM_IN_8_R14") (pintype "power_in"))
      (node (ref "U100") (pin "R9") (pinfunction "VDDARM23_IN_6_R9") (pintype "power_in"))
      (node (ref "U100") (pin "T9") (pinfunction "VDDARM23_IN_7_T9") (pintype "power_in"))
      (node (ref "U100") (pin "U9") (pinfunction "VDDARM23_IN_8_U9") (pintype "power_in"))
    )
    (net (code "14") (name "VDDSOC_CAP") (class "Default")
      (node (ref "C35C") (pin "1") (pinfunction "1_1") (pintype "passive"))
      (node (ref "C36C") (pin "1") (pinfunction "1_1") (pintype "passive"))
      (node (ref "C37C") (pin "1") (pinfunction "1_1") (pintype "passive"))
      (node (ref "C38C") (pin "1") (pinfunction "1_1") (pintype "passive"))
      (node (ref "C39C") (pin "1") (pinfunction "1_1") (pintype "passive"))
      (node (ref "C40C") (pin "1") (pinfunction "1_1") (pintype "passive"))
      (node (ref "C41C") (pin "1") (pinfunction "1_1") (pintype "passive"))
      (node (ref "C42C") (pin "1") (pinfunction "1_1") (pintype "passive"))
      (node (ref "C61C") (pin "1") (pinfunction "1_1") (pintype "passive"))
      (node (ref "C62C") (pin "1") (pinfunction "1_1") (pintype "passive"))
      (node (ref "U100") (pin "N12") (pinfunction "VDD_CACHE_CAP_N12") (pintype "power_in"))
      (node (ref "U100") (pin "R10") (pinfunction "VDDSOC_CAP_1_R10") (pintype "power_in"))
      (node (ref "U100") (pin "T10") (pinfunction "VDDSOC_CAP_2_T10") (pintype "power_in"))
      (node (ref "U100") (pin "T13") (pinfunction "VDDSOC_CAP_3_T13") (pintype "power_in"))
      (node (ref "U100") (pin "T14") (pinfunction "VDDSOC_CAP_4_T14") (pintype "power_in"))
      (node (ref "U100") (pin "U10") (pinfunction "VDDSOC_CAP_5_U10") (pintype "power_in"))
      (node (ref "U100") (pin "U13") (pinfunction "VDDSOC_CAP_6_U13") (pintype "power_in"))
      (node (ref "U100") (pin "U14") (pinfunction "VDDSOC_CAP_7_U14") (pintype "power_in"))
    )
    (net (code "15") (name "VDD_HIGH_CAP") (class "Default")
      (node (ref "C63C") (pin "1") (pinfunction "1_1") (pintype "passive"))
      (node (ref "C64C") (pin "1") (pinfunction "1_1") (pintype "passive"))
      (node (ref "C65C") (pin "1") (pinfunction "1_1") (pintype "passive"))
      (node (ref "C66C") (pin "1") (pinfunction "1_1") (pintype "passive"))
      (node (ref "C74C") (pin "1") (pinfunction "1_1") (pintype "passive"))
      (node (ref "U100") (pin "H10") (pinfunction "VDDHIGH_CAP_1_H10") (pintype "power_in"))
      (node (ref "U100") (pin "J10") (pinfunction "VDDHIGH_CAP_2_J10") (pintype "power_in"))
      (node (ref "U100") (pin "K7") (pinfunction "NVCC_MIPI_K7") (pintype "power_in"))
    )
    (net (code "16") (name "VDD_SOC_IN_SW1C") (class "Default")
      (node (ref "C43C") (pin "1") (pinfunction "1_1") (pintype "passive"))
      (node (ref "C44C") (pin "1") (pinfunction "1_1") (pintype "passive"))
      (node (ref "C45C") (pin "1") (pinfunction "1_1") (pintype "passive"))
      (node (ref "C46C") (pin "1") (pinfunction "1_1") (pintype "passive"))
      (node (ref "C47C") (pin "1") (pinfunction "1_1") (pintype "passive"))
      (node (ref "C48C") (pin "1") (pinfunction "1_1") (pintype "passive"))
      (node (ref "C49C") (pin "1") (pinfunction "1_1") (pintype "passive"))
      (node (ref "C50C") (pin "1") (pinfunction "1_1") (pintype "passive"))
      (node (ref "C51C") (pin "1") (pinfunction "1_1") (pintype "passive"))
      (node (ref "C52C") (pin "1") (pinfunction "1_1") (pintype "passive"))
      (node (ref "U100") (pin "H16") (pinfunction "VDDSOC_IN_1_H16") (pintype "power_in"))
      (node (ref "U100") (pin "J16") (pinfunction "VDDSOC_IN_2_J16") (pintype "power_in"))
      (node (ref "U100") (pin "K16") (pinfunction "VDDSOC_IN_3_K16") (pintype "power_in"))
      (node (ref "U100") (pin "L16") (pinfunction "VDDSOC_IN_4_L16") (pintype "power_in"))
      (node (ref "U100") (pin "M16") (pinfunction "VDDSOC_IN_5_M16") (pintype "power_in"))
      (node (ref "U100") (pin "N16") (pinfunction "VDDSOC_IN_6_N16") (pintype "power_in"))
      (node (ref "U100") (pin "P16") (pinfunction "VDDSOC_IN_7_P16") (pintype "power_in"))
      (node (ref "U100") (pin "R16") (pinfunction "VDDSOC_IN_8_R16") (pintype "power_in"))
      (node (ref "U100") (pin "T16") (pinfunction "VDDSOC_IN_9_T16") (pintype "power_in"))
      (node (ref "U100") (pin "U16") (pinfunction "VDDSOC_IN_10_U16") (pintype "power_in"))
    )
  )
)
